# TPS6300x.net
KiCad netlist of a schematic drawn in EAGLE
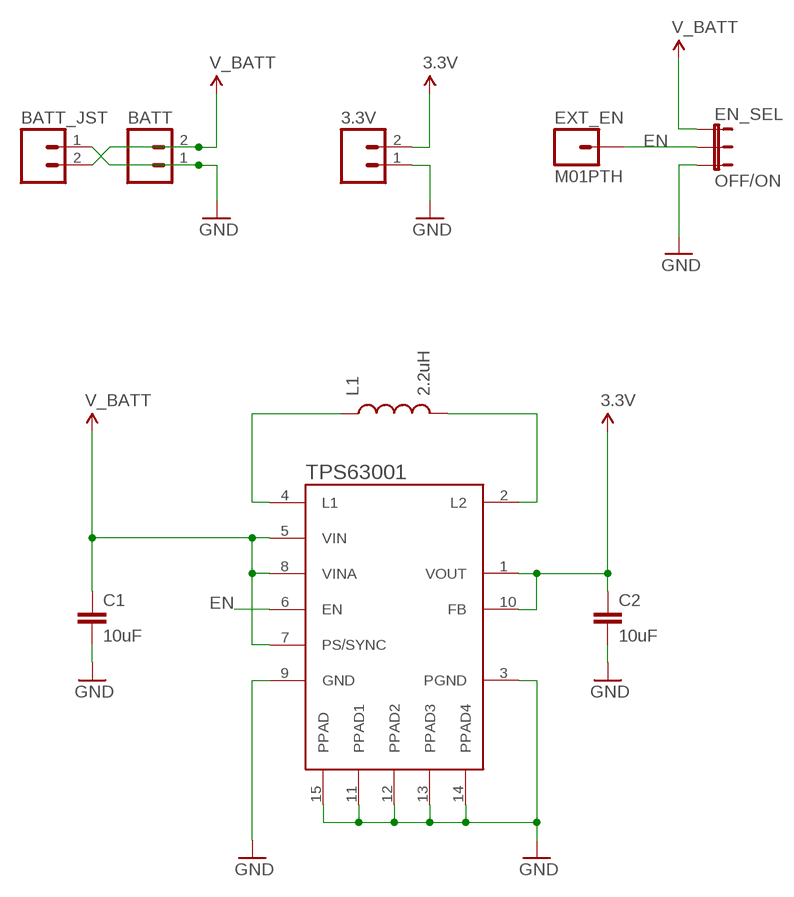
[diagram p0: schematic, sheet 1]

(export (version "E")
  (design (tool "Eeschema 10.0.6"))
  (components
    (comp (ref "3.3V")
      (value "M02PTH")
      (footprint "eagle-import:1X02")
      (libsource (lib "eagle-import") (part "M02PTH"))
    )
    (comp (ref "BATT")
      (value "M02PTH")
      (footprint "eagle-import:1X02")
      (libsource (lib "eagle-import") (part "M02PTH"))
    )
    (comp (ref "BATT_JST")
      (value "M02-JST-2MM-SMT")
      (footprint "eagle-import:JST-2-SMD")
      (libsource (lib "eagle-import") (part "M02-JST-2MM-SMT"))
    )
    (comp (ref "C1")
      (value "10uF")
      (footprint "eagle-import:CAP-2012")
      (libsource (lib "eagle-import") (part "CAP_CER-2012(0805)"))
    )
    (comp (ref "C2")
      (value "10uF")
      (footprint "eagle-import:CAP-2012")
      (libsource (lib "eagle-import") (part "CAP_CER-2012(0805)"))
    )
    (comp (ref "EN_SEL")
      (value "OFF/ON")
      (footprint "eagle-import:SJ_3")
      (libsource (lib "eagle-import") (part "JUMPER-3SMD"))
    )
    (comp (ref "EXT_EN")
      (value "M01PTH")
      (footprint "eagle-import:1X01")
      (libsource (lib "eagle-import") (part "M01PTH"))
    )
    (comp (ref "L1")
      (value "2.2uH")
      (footprint "eagle-import:INDUCTOR-VLF4012A")
      (libsource (lib "eagle-import") (part "INDUCTOR-VLF4012A"))
    )
    (comp (ref "TPS63001")
      (value "TPS6300X")
      (footprint "eagle-import:QFN-10_PAD")
      (libsource (lib "eagle-import") (part "TPS6300X"))
    )
  )
  (nets
    (net (code "1") (name "/EN") (class "Default")
      (node (ref "EN_SEL") (pin "2") (pinfunction "2_2") (pintype "passive"))
      (node (ref "EXT_EN") (pin "1") (pinfunction "1_1") (pintype "passive"))
      (node (ref "TPS63001") (pin "6") (pinfunction "EN_6") (pintype "bidirectional"))
    )
    (net (code "2") (name "3.3V") (class "Default")
      (node (ref "3.3V") (pin "2") (pinfunction "2_2") (pintype "passive"))
      (node (ref "C2") (pin "+") (pinfunction "+_+") (pintype "passive"))
      (node (ref "TPS63001") (pin "1") (pinfunction "VOUT_1") (pintype "bidirectional"))
      (node (ref "TPS63001") (pin "10") (pinfunction "FB_10") (pintype "bidirectional"))
    )
    (net (code "3") (name "GND") (class "Default")
      (node (ref "3.3V") (pin "1") (pinfunction "1_1") (pintype "passive"))
      (node (ref "BATT") (pin "1") (pinfunction "1_1") (pintype "passive"))
      (node (ref "BATT_JST") (pin "1") (pinfunction "2_1") (pintype "passive"))
      (node (ref "C1") (pin "-") (pinfunction "-_-") (pintype "passive"))
      (node (ref "C2") (pin "-") (pinfunction "-_-") (pintype "passive"))
      (node (ref "EN_SEL") (pin "3") (pinfunction "3_3") (pintype "passive"))
      (node (ref "TPS63001") (pin "11") (pinfunction "PPAD1_11") (pintype "bidirectional"))
      (node (ref "TPS63001") (pin "12") (pinfunction "PPAD2_12") (pintype "bidirectional"))
      (node (ref "TPS63001") (pin "13") (pinfunction "PPAD3_13") (pintype "bidirectional"))
      (node (ref "TPS63001") (pin "14") (pinfunction "PPAD4_14") (pintype "bidirectional"))
      (node (ref "TPS63001") (pin "15") (pinfunction "PPAD_15") (pintype "bidirectional"))
      (node (ref "TPS63001") (pin "3") (pinfunction "PGND_3") (pintype "bidirectional"))
      (node (ref "TPS63001") (pin "9") (pinfunction "GND_9") (pintype "bidirectional"))
    )
    (net (code "4") (name "Net-(TPS63001-L1)") (class "Default")
      (node (ref "L1") (pin "2") (pinfunction "2_2") (pintype "passive"))
      (node (ref "TPS63001") (pin "4") (pinfunction "L1_4") (pintype "bidirectional"))
    )
    (net (code "5") (name "Net-(TPS63001-L2)") (class "Default")
      (node (ref "L1") (pin "1") (pinfunction "1_1") (pintype "passive"))
      (node (ref "TPS63001") (pin "2") (pinfunction "L2_2") (pintype "bidirectional"))
    )
    (net (code "6") (name "V_BATT") (class "Default")
      (node (ref "BATT") (pin "2") (pinfunction "2_2") (pintype "passive"))
      (node (ref "BATT_JST") (pin "2") (pinfunction "1_2") (pintype "passive"))
      (node (ref "C1") (pin "+") (pinfunction "+_+") (pintype "passive"))
      (node (ref "EN_SEL") (pin "1") (pinfunction "1_1") (pintype "passive"))
      (node (ref "TPS63001") (pin "5") (pinfunction "VIN_5") (pintype "bidirectional"))
      (node (ref "TPS63001") (pin "7") (pinfunction "PS/SYNC_7") (pintype "bidirectional"))
      (node (ref "TPS63001") (pin "8") (pinfunction "VINA_8") (pintype "bidirectional"))
    )
  )
)
